# ai.net
KiCad netlist of a schematic drawn in Altium Designer
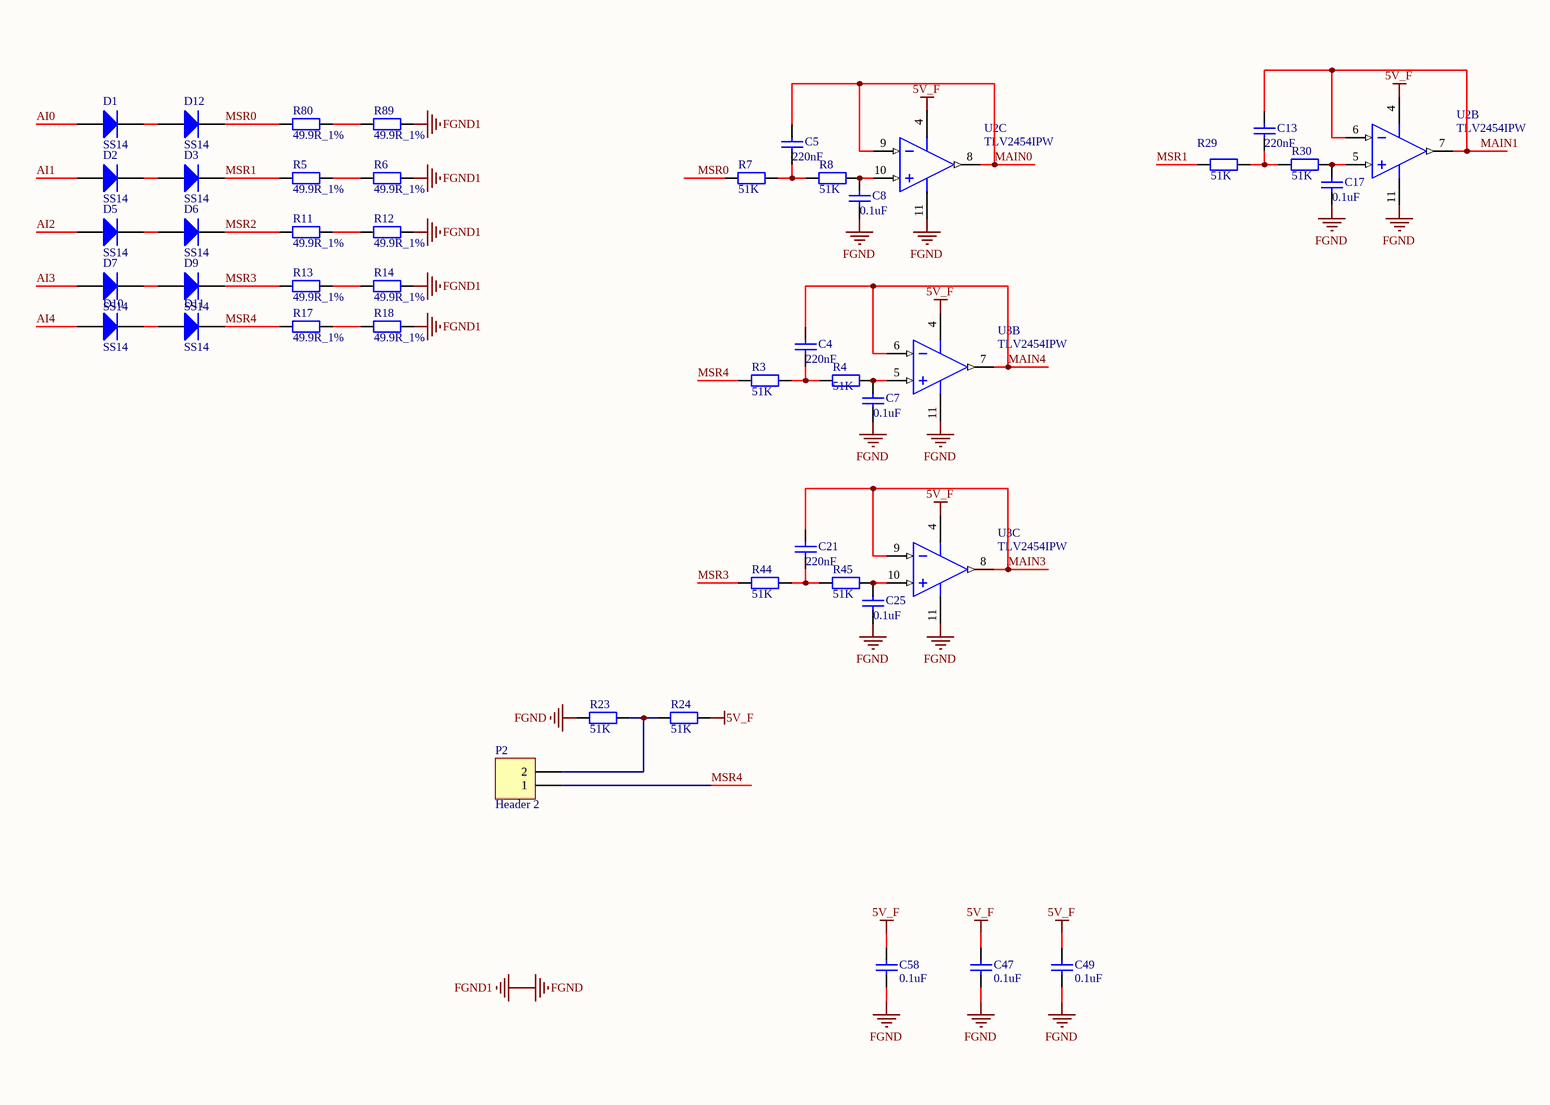
[diagram p0: ai.SchDoc, top left]
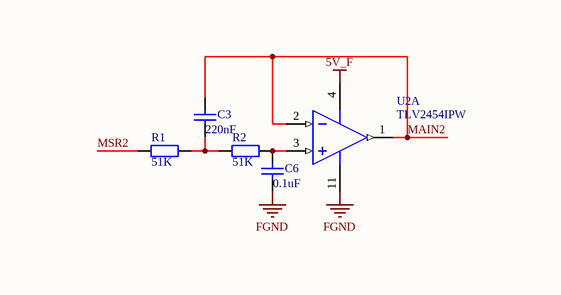
[diagram p1: ai.SchDoc, top right]
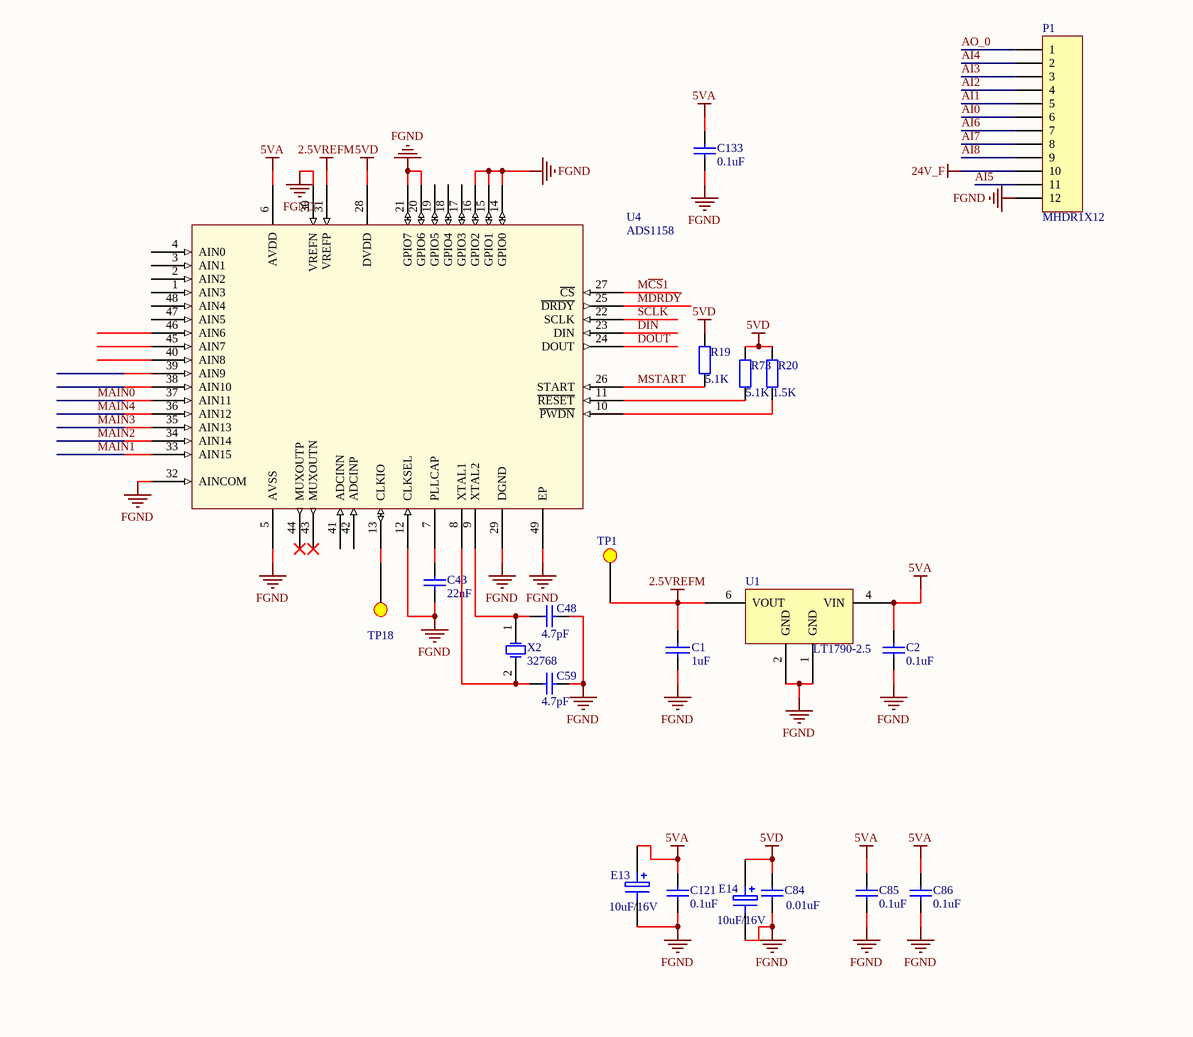
[diagram p2: ai.SchDoc, bottom left]
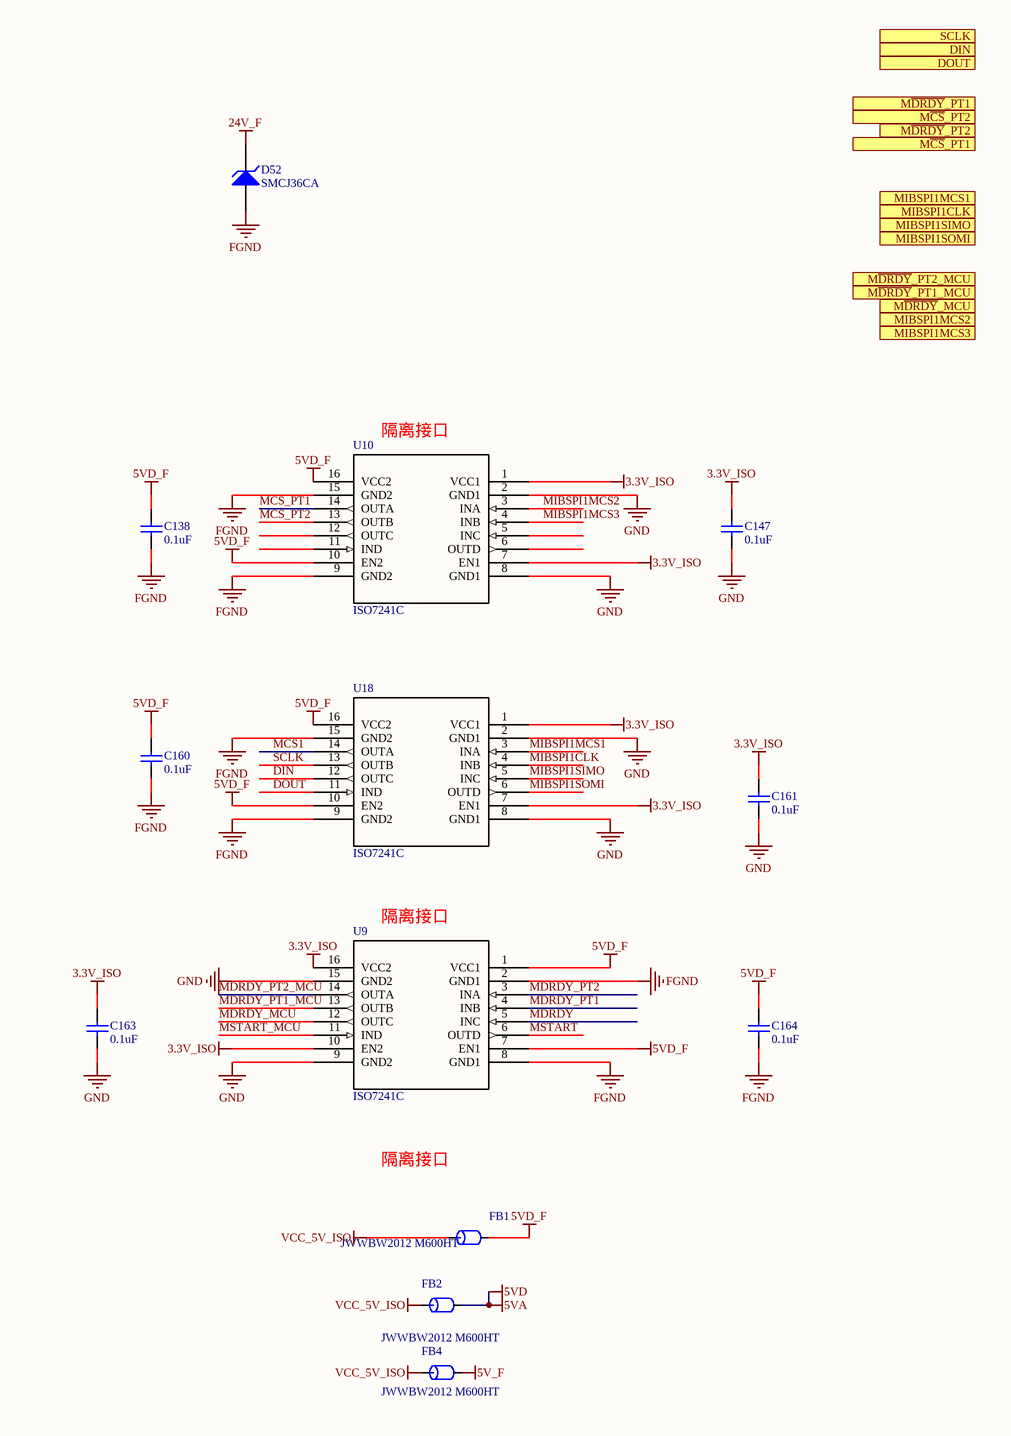
[diagram p3: ai.SchDoc, bottom right]

(export (version "E")
  (design (tool "Eeschema 10.0.6"))
  (components
    (comp (ref "C1")
      (value "1uF")
      (footprint "0603C")
      (description "Capacitor")
      (libsource (lib "*") (part "CAP"))
    )
    (comp (ref "C2")
      (value "0.1uF")
      (footprint "0603C")
      (description "Capacitor")
      (fields (field (name "PUBLISHER") "Altium Limited"))
      (libsource (lib "Miscellaneous Devices") (part "Cap"))
    )
    (comp (ref "C3")
      (value "220nF")
      (footprint "0805C")
      (description "Capacitor")
      (fields (field (name "PUBLISHER") "Altium Limited"))
      (libsource (lib "Miscellaneous Devices") (part "Cap"))
    )
    (comp (ref "C4")
      (value "220nF")
      (footprint "0805C")
      (description "Capacitor")
      (fields (field (name "PUBLISHER") "Altium Limited"))
      (libsource (lib "Miscellaneous Devices") (part "Cap"))
    )
    (comp (ref "C5")
      (value "220nF")
      (footprint "0805C")
      (description "Capacitor")
      (fields (field (name "PUBLISHER") "Altium Limited"))
      (libsource (lib "Miscellaneous Devices") (part "Cap"))
    )
    (comp (ref "C6")
      (value "0.1uF")
      (footprint "0603C")
      (description "Capacitor")
      (fields (field (name "PUBLISHER") "Altium Limited"))
      (libsource (lib "Miscellaneous Devices") (part "Cap"))
    )
    (comp (ref "C7")
      (value "0.1uF")
      (footprint "0603C")
      (description "Capacitor")
      (fields (field (name "PUBLISHER") "Altium Limited"))
      (libsource (lib "Miscellaneous Devices") (part "Cap"))
    )
    (comp (ref "C8")
      (value "0.1uF")
      (footprint "0603C")
      (description "Capacitor")
      (fields (field (name "PUBLISHER") "Altium Limited"))
      (libsource (lib "Miscellaneous Devices") (part "Cap"))
    )
    (comp (ref "C13")
      (value "220nF")
      (footprint "0805C")
      (description "Capacitor")
      (fields (field (name "PUBLISHER") "Altium Limited"))
      (libsource (lib "Miscellaneous Devices") (part "Cap"))
    )
    (comp (ref "C17")
      (value "0.1uF")
      (footprint "0603C")
      (description "Capacitor")
      (fields (field (name "PUBLISHER") "Altium Limited"))
      (libsource (lib "Miscellaneous Devices") (part "Cap"))
    )
    (comp (ref "C21")
      (value "220nF")
      (footprint "0805C")
      (description "Capacitor")
      (fields (field (name "PUBLISHER") "Altium Limited"))
      (libsource (lib "Miscellaneous Devices") (part "Cap"))
    )
    (comp (ref "C25")
      (value "0.1uF")
      (footprint "0603C")
      (description "Capacitor")
      (fields (field (name "PUBLISHER") "Altium Limited"))
      (libsource (lib "Miscellaneous Devices") (part "Cap"))
    )
    (comp (ref "C43")
      (value "22nF")
      (footprint "0805C")
      (description "Capacitor")
      (fields (field (name "PUBLISHER") "Altium Limited"))
      (libsource (lib "Miscellaneous Devices") (part "Cap"))
    )
    (comp (ref "C47")
      (value "0.1uF")
      (footprint "0603C")
      (description "Capacitor")
      (fields (field (name "PUBLISHER") "Altium Limited"))
      (libsource (lib "Miscellaneous Devices") (part "Cap"))
    )
    (comp (ref "C48")
      (value "4.7pF")
      (footprint "0603C")
      (description "Capacitor")
      (fields (field (name "PUBLISHER") "Altium Limited"))
      (libsource (lib "Miscellaneous Devices") (part "Cap"))
    )
    (comp (ref "C49")
      (value "0.1uF")
      (footprint "0603C")
      (description "Capacitor")
      (fields (field (name "PUBLISHER") "Altium Limited"))
      (libsource (lib "Miscellaneous Devices") (part "Cap"))
    )
    (comp (ref "C58")
      (value "0.1uF")
      (footprint "0603C")
      (description "Capacitor")
      (fields (field (name "PUBLISHER") "Altium Limited"))
      (libsource (lib "Miscellaneous Devices") (part "Cap"))
    )
    (comp (ref "C59")
      (value "4.7pF")
      (footprint "0603C")
      (description "Capacitor")
      (fields (field (name "PUBLISHER") "Altium Limited"))
      (libsource (lib "Miscellaneous Devices") (part "Cap"))
    )
    (comp (ref "C84")
      (value "0.01uF")
      (footprint "0603C")
      (description "Capacitor")
      (fields (field (name "PUBLISHER") "Altium Limited"))
      (libsource (lib "Miscellaneous Devices") (part "Cap"))
    )
    (comp (ref "C85")
      (value "0.1uF")
      (footprint "0603C")
      (description "Capacitor")
      (fields (field (name "PUBLISHER") "Altium Limited"))
      (libsource (lib "Miscellaneous Devices") (part "Cap"))
    )
    (comp (ref "C86")
      (value "0.1uF")
      (footprint "0603C")
      (description "Capacitor")
      (fields (field (name "PUBLISHER") "Altium Limited"))
      (libsource (lib "Miscellaneous Devices") (part "Cap"))
    )
    (comp (ref "C121")
      (value "0.1uF")
      (footprint "0603C")
      (description "Capacitor")
      (fields (field (name "PUBLISHER") "Altium Limited"))
      (libsource (lib "Miscellaneous Devices") (part "Cap"))
    )
    (comp (ref "C133")
      (value "0.1uF")
      (footprint "0603C")
      (description "Capacitor")
      (fields (field (name "PUBLISHER") "Altium Limited"))
      (libsource (lib "Miscellaneous Devices") (part "Cap"))
    )
    (comp (ref "C138")
      (value "0.1uF")
      (footprint "0603C")
      (description "Capacitor")
      (fields (field (name "PUBLISHER") "Altium Limited"))
      (libsource (lib "Miscellaneous Devices") (part "Cap"))
    )
    (comp (ref "C147")
      (value "0.1uF")
      (footprint "0603C")
      (description "Capacitor")
      (fields (field (name "PUBLISHER") "Altium Limited"))
      (libsource (lib "Miscellaneous Devices") (part "Cap"))
    )
    (comp (ref "C160")
      (value "0.1uF")
      (footprint "0603C")
      (description "Capacitor")
      (fields (field (name "PUBLISHER") "Altium Limited"))
      (libsource (lib "Miscellaneous Devices") (part "Cap"))
    )
    (comp (ref "C161")
      (value "0.1uF")
      (footprint "0603C")
      (description "Capacitor")
      (fields (field (name "PUBLISHER") "Altium Limited"))
      (libsource (lib "Miscellaneous Devices") (part "Cap"))
    )
    (comp (ref "C163")
      (value "0.1uF")
      (footprint "0603C")
      (description "Capacitor")
      (fields (field (name "PUBLISHER") "Altium Limited"))
      (libsource (lib "Miscellaneous Devices") (part "Cap"))
    )
    (comp (ref "C164")
      (value "0.1uF")
      (footprint "0603C")
      (description "Capacitor")
      (fields (field (name "PUBLISHER") "Altium Limited"))
      (libsource (lib "Miscellaneous Devices") (part "Cap"))
    )
    (comp (ref "D1")
      (value "SS14")
      (footprint "DO-214AC")
      (description "Default Diode")
      (fields (field (name "PUBLISHER") "Altium Limited"))
      (libsource (lib "Miscellaneous Devices") (part "Diode"))
    )
    (comp (ref "D2")
      (value "SS14")
      (footprint "DO-214AC")
      (description "Default Diode")
      (fields (field (name "PUBLISHER") "Altium Limited"))
      (libsource (lib "Miscellaneous Devices") (part "Diode"))
    )
    (comp (ref "D3")
      (value "SS14")
      (footprint "DO-214AC")
      (description "Default Diode")
      (fields (field (name "PUBLISHER") "Altium Limited"))
      (libsource (lib "Miscellaneous Devices") (part "Diode"))
    )
    (comp (ref "D5")
      (value "SS14")
      (footprint "DO-214AC")
      (description "Default Diode")
      (fields (field (name "PUBLISHER") "Altium Limited"))
      (libsource (lib "Miscellaneous Devices") (part "Diode"))
    )
    (comp (ref "D6")
      (value "SS14")
      (footprint "DO-214AC")
      (description "Default Diode")
      (fields (field (name "PUBLISHER") "Altium Limited"))
      (libsource (lib "Miscellaneous Devices") (part "Diode"))
    )
    (comp (ref "D7")
      (value "SS14")
      (footprint "DO-214AC")
      (description "Default Diode")
      (fields (field (name "PUBLISHER") "Altium Limited"))
      (libsource (lib "Miscellaneous Devices") (part "Diode"))
    )
    (comp (ref "D9")
      (value "SS14")
      (footprint "DO-214AC")
      (description "Default Diode")
      (fields (field (name "PUBLISHER") "Altium Limited"))
      (libsource (lib "Miscellaneous Devices") (part "Diode"))
    )
    (comp (ref "D10")
      (value "SS14")
      (footprint "DO-214AC")
      (description "Default Diode")
      (fields (field (name "PUBLISHER") "Altium Limited"))
      (libsource (lib "Miscellaneous Devices") (part "Diode"))
    )
    (comp (ref "D11")
      (value "SS14")
      (footprint "DO-214AC")
      (description "Default Diode")
      (fields (field (name "PUBLISHER") "Altium Limited"))
      (libsource (lib "Miscellaneous Devices") (part "Diode"))
    )
    (comp (ref "D12")
      (value "SS14")
      (footprint "DO-214AC")
      (description "Default Diode")
      (fields (field (name "PUBLISHER") "Altium Limited"))
      (libsource (lib "Miscellaneous Devices") (part "Diode"))
    )
    (comp (ref "D52")
      (value "SMCJ36CA")
      (footprint "SMC")
      (description "SMBJ36CA")
      (fields (field (name "PUBLISHER") "Altium Limited"))
      (libsource (lib "Miscellaneous Devices") (part "D Zener"))
    )
    (comp (ref "E13")
      (value "10uF/16V")
      (footprint "C3528")
      (description "Electrolytic Capacitor")
      (libsource (lib "*") (part "ELECTRO1"))
    )
    (comp (ref "E14")
      (value "10uF/16V")
      (footprint "C3528")
      (description "Electrolytic Capacitor")
      (libsource (lib "*") (part "ELECTRO1"))
    )
    (comp (ref "FB1")
      (value "JWWBW2012 M600HT")
      (footprint "0805R")
      (libsource (lib "Schlib_20110825") (part "FB"))
    )
    (comp (ref "FB2")
      (value "JWWBW2012 M600HT")
      (footprint "0805R")
      (libsource (lib "Schlib_20110825") (part "FB"))
    )
    (comp (ref "FB4")
      (value "JWWBW2012 M600HT")
      (footprint "0805R")
      (libsource (lib "Schlib_20110825") (part "FB"))
    )
    (comp (ref "P1")
      (value "MHDR1X12")
      (footprint "2ETYR-5.08-12P-14-100")
      (description "Header, 12-Pin")
      (fields (field (name "PUBLISHER") "Altium Limited"))
      (libsource (lib "Miscellaneous Connectors") (part "MHDR1X12"))
    )
    (comp (ref "P2")
      (value "Header 2")
      (footprint "HDR1X2")
      (description "Header, 2-Pin")
      (fields (field (name "PUBLISHER") "Altium Limited"))
      (libsource (lib "Miscellaneous Connectors") (part "Header 2"))
    )
    (comp (ref "R1") (value "51K") (footprint "0603R") (libsource (lib "MQlibrary") (part "Res0805M")))
    (comp (ref "R2") (value "51K") (footprint "0603R") (libsource (lib "MQlibrary") (part "Res0805M")))
    (comp (ref "R3") (value "51K") (footprint "0603R") (libsource (lib "MQlibrary") (part "Res0805M")))
    (comp (ref "R4") (value "51K") (footprint "0603R") (libsource (lib "MQlibrary") (part "Res0805M")))
    (comp (ref "R5") (value "49.9R_1%") (footprint "0805R") (libsource (lib "MQlibrary") (part "Res0805M")))
    (comp (ref "R6") (value "49.9R_1%") (footprint "0805R") (libsource (lib "MQlibrary") (part "Res0805M")))
    (comp (ref "R7") (value "51K") (footprint "0603R") (libsource (lib "MQlibrary") (part "Res0805M")))
    (comp (ref "R8") (value "51K") (footprint "0603R") (libsource (lib "MQlibrary") (part "Res0805M")))
    (comp (ref "R11") (value "49.9R_1%") (footprint "0805R") (libsource (lib "MQlibrary") (part "Res0805M")))
    (comp (ref "R12") (value "49.9R_1%") (footprint "0805R") (libsource (lib "MQlibrary") (part "Res0805M")))
    (comp (ref "R13") (value "49.9R_1%") (footprint "0805R") (libsource (lib "MQlibrary") (part "Res0805M")))
    (comp (ref "R14") (value "49.9R_1%") (footprint "0805R") (libsource (lib "MQlibrary") (part "Res0805M")))
    (comp (ref "R17") (value "49.9R_1%") (footprint "0805R") (libsource (lib "MQlibrary") (part "Res0805M")))
    (comp (ref "R18") (value "49.9R_1%") (footprint "0805R") (libsource (lib "MQlibrary") (part "Res0805M")))
    (comp (ref "R19") (value "5.1K") (footprint "0603R") (libsource (lib "") (part "Res0805M_2")))
    (comp (ref "R20") (value "1.5K") (footprint "0603R") (libsource (lib "") (part "Res0805M_2")))
    (comp (ref "R23") (value "51K") (footprint "0603R") (libsource (lib "") (part "Res0805M_1")))
    (comp (ref "R24") (value "51K") (footprint "0603R") (libsource (lib "") (part "Res0805M_1")))
    (comp (ref "R29") (value "51K") (footprint "0603R") (libsource (lib "MQlibrary") (part "Res0805M")))
    (comp (ref "R30") (value "51K") (footprint "0603R") (libsource (lib "MQlibrary") (part "Res0805M")))
    (comp (ref "R44") (value "51K") (footprint "0603R") (libsource (lib "MQlibrary") (part "Res0805M")))
    (comp (ref "R45") (value "51K") (footprint "0603R") (libsource (lib "MQlibrary") (part "Res0805M")))
    (comp (ref "R73") (value "5.1K") (footprint "0603R") (libsource (lib "") (part "Res0805M_2")))
    (comp (ref "R80") (value "49.9R_1%") (footprint "0805R") (libsource (lib "MQlibrary") (part "Res0805M")))
    (comp (ref "R89") (value "49.9R_1%") (footprint "0805R") (libsource (lib "MQlibrary") (part "Res0805M")))
    (comp (ref "TP1")
      (value "TEST_POINT")
      (footprint "TPD")
      (libsource (lib "基带芯片OEM板_V1P0_张猛_20120921") (part "TEST_POINT"))
    )
    (comp (ref "TP18")
      (value "TEST_POINT")
      (footprint "TPD")
      (libsource (lib "基带芯片OEM板_V1P0_张猛_20120921") (part "TEST_POINT"))
    )
    (comp (ref "U1")
      (value "LT1790-2.5")
      (footprint "SOT23-6")
      (description "2.5V Micropower SOT-23  Low Dropout Reference")
      (libsource (lib "Schlib") (part "LT1790-2.5"))
    )
    (comp (ref "U2")
      (value "TLV2454IPW")
      (footprint "TSSOP14")
      (description "Quad High-speed, Ultra Low-power, Single-Supply TTL comparator")
      (fields (field (name "PUBLISHER") "Altium Limited"))
      (libsource (lib "Maxim Analog Comparator") (part "MAX908EPD"))
    )
    (comp (ref "U3")
      (value "TLV2454IPW")
      (footprint "TSSOP14")
      (description "Quad High-speed, Ultra Low-power, Single-Supply TTL comparator")
      (fields (field (name "PUBLISHER") "Altium Limited"))
      (libsource (lib "Maxim Analog Comparator") (part "MAX908EPD"))
    )
    (comp (ref "U4")
      (value "ADS1158")
      (footprint "S-PVFQN-N48")
      (description "16-Channel, 16-Bit Analog-to-Digital Converter")
      (libsource (lib "Schlib") (part "ADS1158"))
    )
    (comp (ref "U9") (value "ISO7241C") (footprint "SOIC16") (libsource (lib "DI16") (part "ISO7241C")))
    (comp (ref "U10") (value "ISO7241C") (footprint "SOIC16") (libsource (lib "DI16") (part "ISO7241C")))
    (comp (ref "U18") (value "ISO7241C") (footprint "SOIC16") (libsource (lib "DI16") (part "ISO7241C")))
    (comp (ref "X2")
      (value "32768")
      (footprint "A")
      (description "Crystal Oscillator")
      (fields (field (name "PUBLISHER") "Altium Limited"))
      (libsource (lib "Miscellaneous Devices") (part "XTAL"))
    )
  )
  (nets
    (net (code "1") (name "/AI0") (class "Default")
      (node (ref "D1") (pin "1") (pinfunction "A_1") (pintype "passive"))
      (node (ref "P1") (pin "6") (pinfunction "6_6") (pintype "passive"))
    )
    (net (code "2") (name "/AI1") (class "Default")
      (node (ref "D2") (pin "1") (pinfunction "A_1") (pintype "passive"))
      (node (ref "P1") (pin "5") (pinfunction "5_5") (pintype "passive"))
    )
    (net (code "3") (name "/AI2") (class "Default")
      (node (ref "D5") (pin "1") (pinfunction "A_1") (pintype "passive"))
      (node (ref "P1") (pin "4") (pinfunction "4_4") (pintype "passive"))
    )
    (net (code "4") (name "/AI3") (class "Default")
      (node (ref "D7") (pin "1") (pinfunction "A_1") (pintype "passive"))
      (node (ref "P1") (pin "3") (pinfunction "3_3") (pintype "passive"))
    )
    (net (code "5") (name "/AI4") (class "Default")
      (node (ref "D10") (pin "1") (pinfunction "A_1") (pintype "passive"))
      (node (ref "P1") (pin "2") (pinfunction "2_2") (pintype "passive"))
    )
    (net (code "6") (name "/AI5") (class "Default")
      (node (ref "P1") (pin "11") (pinfunction "11_11") (pintype "passive"))
    )
    (net (code "7") (name "/AI6") (class "Default")
      (node (ref "P1") (pin "7") (pinfunction "7_7") (pintype "passive"))
    )
    (net (code "8") (name "/AI7") (class "Default")
      (node (ref "P1") (pin "8") (pinfunction "8_8") (pintype "passive"))
    )
    (net (code "9") (name "/AI8") (class "Default")
      (node (ref "P1") (pin "9") (pinfunction "9_9") (pintype "passive"))
    )
    (net (code "10") (name "/AO_0") (class "Default")
      (node (ref "P1") (pin "1") (pinfunction "1_1") (pintype "passive"))
    )
    (net (code "11") (name "/DIN") (class "Default")
      (node (ref "U18") (pin "12") (pinfunction "OUTC_12") (pintype "output"))
      (node (ref "U4") (pin "23") (pinfunction "DIN_23") (pintype "input"))
    )
    (net (code "12") (name "/DOUT") (class "Default")
      (node (ref "U18") (pin "11") (pinfunction "IND_11") (pintype "input"))
      (node (ref "U4") (pin "24") (pinfunction "DOUT_24") (pintype "output"))
    )
    (net (code "13") (name "/MAIN0") (class "Default")
      (node (ref "C5") (pin "2") (pinfunction "2_2") (pintype "passive"))
      (node (ref "U2") (pin "8") (pinfunction "OUT_8") (pintype "output"))
      (node (ref "U2") (pin "9") (pinfunction "IN-_9") (pintype "input"))
      (node (ref "U4") (pin "37") (pinfunction "AIN11_37") (pintype "input"))
    )
    (net (code "14") (name "/MAIN1") (class "Default")
      (node (ref "C13") (pin "2") (pinfunction "2_2") (pintype "passive"))
      (node (ref "U2") (pin "6") (pinfunction "IN-_6") (pintype "input"))
      (node (ref "U2") (pin "7") (pinfunction "OUT_7") (pintype "output"))
      (node (ref "U4") (pin "33") (pinfunction "AIN15_33") (pintype "input"))
    )
    (net (code "15") (name "/MAIN2") (class "Default")
      (node (ref "C3") (pin "2") (pinfunction "2_2") (pintype "passive"))
      (node (ref "U2") (pin "1") (pinfunction "OUT_1") (pintype "output"))
      (node (ref "U2") (pin "2") (pinfunction "IN-_2") (pintype "input"))
      (node (ref "U4") (pin "34") (pinfunction "AIN14_34") (pintype "input"))
    )
    (net (code "16") (name "/MAIN3") (class "Default")
      (node (ref "C21") (pin "2") (pinfunction "2_2") (pintype "passive"))
      (node (ref "U3") (pin "8") (pinfunction "OUT_8") (pintype "output"))
      (node (ref "U3") (pin "9") (pinfunction "IN-_9") (pintype "input"))
      (node (ref "U4") (pin "35") (pinfunction "AIN13_35") (pintype "input"))
    )
    (net (code "17") (name "/MAIN4") (class "Default")
      (node (ref "C4") (pin "2") (pinfunction "2_2") (pintype "passive"))
      (node (ref "U3") (pin "6") (pinfunction "IN-_6") (pintype "input"))
      (node (ref "U3") (pin "7") (pinfunction "OUT_7") (pintype "output"))
      (node (ref "U4") (pin "36") (pinfunction "AIN12_36") (pintype "input"))
    )
    (net (code "18") (name "/MIBSPI1CLK") (class "Default")
      (node (ref "U18") (pin "4") (pinfunction "INB_4") (pintype "input"))
    )
    (net (code "19") (name "/MIBSPI1MCS1") (class "Default")
      (node (ref "U18") (pin "3") (pinfunction "INA_3") (pintype "input"))
    )
    (net (code "20") (name "/MIBSPI1MCS2") (class "Default")
      (node (ref "U10") (pin "3") (pinfunction "INA_3") (pintype "input"))
    )
    (net (code "21") (name "/MIBSPI1MCS3") (class "Default")
      (node (ref "U10") (pin "4") (pinfunction "INB_4") (pintype "input"))
    )
    (net (code "22") (name "/MIBSPI1SIMO") (class "Default")
      (node (ref "U18") (pin "5") (pinfunction "INC_5") (pintype "input"))
    )
    (net (code "23") (name "/MIBSPI1SOMI") (class "Default")
      (node (ref "U18") (pin "6") (pinfunction "OUTD_6") (pintype "output"))
    )
    (net (code "24") (name "/MSR0") (class "Default")
      (node (ref "D12") (pin "2") (pinfunction "K_2") (pintype "passive"))
      (node (ref "R7") (pin "2") (pinfunction "2_2") (pintype "passive"))
      (node (ref "R80") (pin "2") (pinfunction "2_2") (pintype "passive"))
    )
    (net (code "25") (name "/MSR1") (class "Default")
      (node (ref "D3") (pin "2") (pinfunction "K_2") (pintype "passive"))
      (node (ref "R29") (pin "2") (pinfunction "2_2") (pintype "passive"))
      (node (ref "R5") (pin "2") (pinfunction "2_2") (pintype "passive"))
    )
    (net (code "26") (name "/MSR2") (class "Default")
      (node (ref "D6") (pin "2") (pinfunction "K_2") (pintype "passive"))
      (node (ref "R1") (pin "2") (pinfunction "2_2") (pintype "passive"))
      (node (ref "R11") (pin "2") (pinfunction "2_2") (pintype "passive"))
    )
    (net (code "27") (name "/MSR3") (class "Default")
      (node (ref "D9") (pin "2") (pinfunction "K_2") (pintype "passive"))
      (node (ref "R13") (pin "2") (pinfunction "2_2") (pintype "passive"))
      (node (ref "R44") (pin "2") (pinfunction "2_2") (pintype "passive"))
    )
    (net (code "28") (name "/MSR4") (class "Default")
      (node (ref "D11") (pin "2") (pinfunction "K_2") (pintype "passive"))
      (node (ref "P2") (pin "1") (pinfunction "1_1") (pintype "passive"))
      (node (ref "R17") (pin "2") (pinfunction "2_2") (pintype "passive"))
      (node (ref "R3") (pin "2") (pinfunction "2_2") (pintype "passive"))
    )
    (net (code "29") (name "/MSTART") (class "Default")
      (node (ref "R19") (pin "2") (pinfunction "2_2") (pintype "passive"))
      (node (ref "U4") (pin "26") (pinfunction "START_26") (pintype "input"))
      (node (ref "U9") (pin "6") (pinfunction "OUTD_6") (pintype "output"))
    )
    (net (code "30") (name "/MSTART_MCU") (class "Default")
      (node (ref "U9") (pin "11") (pinfunction "IND_11") (pintype "input"))
    )
    (net (code "31") (name "/M~{CS}1") (class "Default")
      (node (ref "U18") (pin "14") (pinfunction "OUTA_14") (pintype "output"))
      (node (ref "U4") (pin "27") (pinfunction "~{CS}_27") (pintype "input"))
    )
    (net (code "32") (name "/M~{CS}_PT1") (class "Default")
      (node (ref "U10") (pin "14") (pinfunction "OUTA_14") (pintype "output"))
    )
    (net (code "33") (name "/M~{CS}_PT2") (class "Default")
      (node (ref "U10") (pin "13") (pinfunction "OUTB_13") (pintype "output"))
    )
    (net (code "34") (name "/M~{DRDY}") (class "Default")
      (node (ref "U4") (pin "25") (pinfunction "~{DRDY}_25") (pintype "output"))
      (node (ref "U9") (pin "5") (pinfunction "INC_5") (pintype "input"))
    )
    (net (code "35") (name "/M~{DRDY}_MCU") (class "Default")
      (node (ref "U9") (pin "12") (pinfunction "OUTC_12") (pintype "output"))
    )
    (net (code "36") (name "/M~{DRDY}_PT1") (class "Default")
      (node (ref "U9") (pin "4") (pinfunction "INB_4") (pintype "input"))
    )
    (net (code "37") (name "/M~{DRDY}_PT1_MCU") (class "Default")
      (node (ref "U9") (pin "13") (pinfunction "OUTB_13") (pintype "output"))
    )
    (net (code "38") (name "/M~{DRDY}_PT2") (class "Default")
      (node (ref "U9") (pin "3") (pinfunction "INA_3") (pintype "input"))
    )
    (net (code "39") (name "/M~{DRDY}_PT2_MCU") (class "Default")
      (node (ref "U9") (pin "14") (pinfunction "OUTA_14") (pintype "output"))
    )
    (net (code "40") (name "/SCLK") (class "Default")
      (node (ref "U18") (pin "13") (pinfunction "OUTB_13") (pintype "output"))
      (node (ref "U4") (pin "22") (pinfunction "SCLK_22") (pintype "input"))
    )
    (net (code "41") (name "2.5VREFM") (class "Default")
      (node (ref "C1") (pin "1") (pinfunction "1_1") (pintype "passive"))
      (node (ref "TP1") (pin "1") (pinfunction "1_1") (pintype "passive"))
      (node (ref "U1") (pin "6") (pinfunction "VOUT_6") (pintype "power_in"))
      (node (ref "U4") (pin "31") (pinfunction "VREFP_31") (pintype "input"))
    )
    (net (code "42") (name "3.3V_ISO") (class "Default")
      (node (ref "C147") (pin "2") (pinfunction "2_2") (pintype "passive"))
      (node (ref "C161") (pin "2") (pinfunction "2_2") (pintype "passive"))
      (node (ref "C163") (pin "2") (pinfunction "2_2") (pintype "passive"))
      (node (ref "U10") (pin "1") (pinfunction "VCC1_1") (pintype "power_in"))
      (node (ref "U10") (pin "7") (pinfunction "EN1_7") (pintype "passive"))
      (node (ref "U18") (pin "1") (pinfunction "VCC1_1") (pintype "power_in"))
      (node (ref "U18") (pin "7") (pinfunction "EN1_7") (pintype "passive"))
      (node (ref "U9") (pin "10") (pinfunction "EN2_10") (pintype "passive"))
      (node (ref "U9") (pin "16") (pinfunction "VCC2_16") (pintype "power_in"))
    )
    (net (code "43") (name "5VA") (class "Default")
      (node (ref "C121") (pin "2") (pinfunction "2_2") (pintype "passive"))
      (node (ref "C133") (pin "2") (pinfunction "2_2") (pintype "passive"))
      (node (ref "C2") (pin "2") (pinfunction "2_2") (pintype "passive"))
      (node (ref "C84") (pin "2") (pinfunction "2_2") (pintype "passive"))
      (node (ref "C85") (pin "2") (pinfunction "2_2") (pintype "passive"))
      (node (ref "C86") (pin "2") (pinfunction "2_2") (pintype "passive"))
      (node (ref "E13") (pin "1") (pinfunction "1_1") (pintype "passive"))
      (node (ref "E14") (pin "1") (pinfunction "1_1") (pintype "passive"))
      (node (ref "FB2") (pin "2") (pintype "passive"))
      (node (ref "R19") (pin "1") (pinfunction "1_1") (pintype "passive"))
      (node (ref "R20") (pin "1") (pinfunction "1_1") (pintype "passive"))
      (node (ref "R73") (pin "1") (pinfunction "1_1") (pintype "passive"))
      (node (ref "U1") (pin "4") (pinfunction "VIN_4") (pintype "power_in"))
      (node (ref "U4") (pin "28") (pinfunction "DVDD_28") (pintype "power_in"))
      (node (ref "U4") (pin "6") (pinfunction "AVDD_6") (pintype "passive"))
    )
    (net (code "44") (name "5VD_F") (class "Default")
      (node (ref "C138") (pin "2") (pinfunction "2_2") (pintype "passive"))
      (node (ref "C160") (pin "2") (pinfunction "2_2") (pintype "passive"))
      (node (ref "C164") (pin "2") (pinfunction "2_2") (pintype "passive"))
      (node (ref "FB1") (pin "2") (pintype "passive"))
      (node (ref "U10") (pin "10") (pinfunction "EN2_10") (pintype "passive"))
      (node (ref "U10") (pin "16") (pinfunction "VCC2_16") (pintype "power_in"))
      (node (ref "U18") (pin "10") (pinfunction "EN2_10") (pintype "passive"))
      (node (ref "U18") (pin "16") (pinfunction "VCC2_16") (pintype "power_in"))
      (node (ref "U9") (pin "1") (pinfunction "VCC1_1") (pintype "power_in"))
      (node (ref "U9") (pin "7") (pinfunction "EN1_7") (pintype "passive"))
    )
    (net (code "45") (name "5V_F") (class "Default")
      (node (ref "C47") (pin "2") (pinfunction "2_2") (pintype "passive"))
      (node (ref "C49") (pin "2") (pinfunction "2_2") (pintype "passive"))
      (node (ref "C58") (pin "2") (pinfunction "2_2") (pintype "passive"))
      (node (ref "FB4") (pin "2") (pintype "passive"))
      (node (ref "R24") (pin "2") (pinfunction "2_2") (pintype "passive"))
      (node (ref "U2") (pin "4") (pinfunction "V+_4") (pintype "power_in"))
      (node (ref "U3") (pin "4") (pinfunction "V+_4") (pintype "power_in"))
    )
    (net (code "46") (name "24V_F") (class "Default")
      (node (ref "D52") (pin "2") (pinfunction "K_2") (pintype "passive"))
      (node (ref "P1") (pin "10") (pinfunction "10_10") (pintype "passive"))
    )
    (net (code "47") (name "FGND") (class "Default")
      (node (ref "C1") (pin "2") (pinfunction "2_2") (pintype "passive"))
      (node (ref "C121") (pin "1") (pinfunction "1_1") (pintype "passive"))
      (node (ref "C133") (pin "1") (pinfunction "1_1") (pintype "passive"))
      (node (ref "C138") (pin "1") (pinfunction "1_1") (pintype "passive"))
      (node (ref "C160") (pin "1") (pinfunction "1_1") (pintype "passive"))
      (node (ref "C164") (pin "1") (pinfunction "1_1") (pintype "passive"))
      (node (ref "C17") (pin "1") (pinfunction "1_1") (pintype "passive"))
      (node (ref "C2") (pin "1") (pinfunction "1_1") (pintype "passive"))
      (node (ref "C25") (pin "1") (pinfunction "1_1") (pintype "passive"))
      (node (ref "C43") (pin "2") (pinfunction "2_2") (pintype "passive"))
      (node (ref "C47") (pin "1") (pinfunction "1_1") (pintype "passive"))
      (node (ref "C48") (pin "2") (pinfunction "2_2") (pintype "passive"))
      (node (ref "C49") (pin "1") (pinfunction "1_1") (pintype "passive"))
      (node (ref "C58") (pin "1") (pinfunction "1_1") (pintype "passive"))
      (node (ref "C59") (pin "2") (pinfunction "2_2") (pintype "passive"))
      (node (ref "C6") (pin "1") (pinfunction "1_1") (pintype "passive"))
      (node (ref "C7") (pin "1") (pinfunction "1_1") (pintype "passive"))
      (node (ref "C8") (pin "1") (pinfunction "1_1") (pintype "passive"))
      (node (ref "C84") (pin "1") (pinfunction "1_1") (pintype "passive"))
      (node (ref "C85") (pin "1") (pinfunction "1_1") (pintype "passive"))
      (node (ref "C86") (pin "1") (pinfunction "1_1") (pintype "passive"))
      (node (ref "D52") (pin "1") (pinfunction "A_1") (pintype "passive"))
      (node (ref "E13") (pin "2") (pinfunction "2_2") (pintype "passive"))
      (node (ref "E14") (pin "2") (pinfunction "2_2") (pintype "passive"))
      (node (ref "P1") (pin "12") (pinfunction "12_12") (pintype "passive"))
      (node (ref "R12") (pin "1") (pinfunction "1_1") (pintype "passive"))
      (node (ref "R14") (pin "1") (pinfunction "1_1") (pintype "passive"))
      (node (ref "R18") (pin "1") (pinfunction "1_1") (pintype "passive"))
      (node (ref "R23") (pin "1") (pinfunction "1_1") (pintype "passive"))
      (node (ref "R6") (pin "1") (pinfunction "1_1") (pintype "passive"))
      (node (ref "R89") (pin "1") (pinfunction "1_1") (pintype "passive"))
      (node (ref "U1") (pin "1") (pinfunction "GND_1") (pintype "power_in"))
      (node (ref "U1") (pin "2") (pinfunction "GND_2") (pintype "power_in"))
      (node (ref "U10") (pin "15") (pinfunction "GND2_15") (pintype "power_in"))
      (node (ref "U10") (pin "9") (pinfunction "GND2_9") (pintype "power_in"))
      (node (ref "U18") (pin "15") (pinfunction "GND2_15") (pintype "power_in"))
      (node (ref "U18") (pin "9") (pinfunction "GND2_9") (pintype "power_in"))
      (node (ref "U2") (pin "11") (pinfunction "GND_11") (pintype "power_in"))
      (node (ref "U3") (pin "11") (pinfunction "GND_11") (pintype "power_in"))
      (node (ref "U4") (pin "12") (pinfunction "CLKSEL_12") (pintype "input"))
      (node (ref "U4") (pin "14") (pinfunction "GPIO0_14") (pintype "bidirectional"))
      (node (ref "U4") (pin "15") (pinfunction "GPIO1_15") (pintype "bidirectional"))
      (node (ref "U4") (pin "16") (pinfunction "GPIO2_16") (pintype "bidirectional"))
      (node (ref "U4") (pin "20") (pinfunction "GPIO6_20") (pintype "bidirectional"))
      (node (ref "U4") (pin "21") (pinfunction "GPIO7_21") (pintype "bidirectional"))
      (node (ref "U4") (pin "29") (pinfunction "DGND_29") (pintype "power_in"))
      (node (ref "U4") (pin "30") (pinfunction "VREFN_30") (pintype "input"))
      (node (ref "U4") (pin "32") (pinfunction "AINCOM_32") (pintype "input"))
      (node (ref "U4") (pin "49") (pinfunction "EP_49") (pintype "passive"))
      (node (ref "U4") (pin "5") (pinfunction "AVSS_5") (pintype "power_in"))
      (node (ref "U9") (pin "2") (pinfunction "GND1_2") (pintype "power_in"))
      (node (ref "U9") (pin "8") (pinfunction "GND1_8") (pintype "power_in"))
    )
    (net (code "48") (name "GND") (class "Default")
      (node (ref "C147") (pin "1") (pinfunction "1_1") (pintype "passive"))
      (node (ref "C161") (pin "1") (pinfunction "1_1") (pintype "passive"))
      (node (ref "C163") (pin "1") (pinfunction "1_1") (pintype "passive"))
      (node (ref "U10") (pin "2") (pinfunction "GND1_2") (pintype "power_in"))
      (node (ref "U10") (pin "8") (pinfunction "GND1_8") (pintype "power_in"))
      (node (ref "U18") (pin "2") (pinfunction "GND1_2") (pintype "power_in"))
      (node (ref "U18") (pin "8") (pinfunction "GND1_8") (pintype "power_in"))
      (node (ref "U9") (pin "15") (pinfunction "GND2_15") (pintype "power_in"))
      (node (ref "U9") (pin "9") (pinfunction "GND2_9") (pintype "power_in"))
    )
    (net (code "49") (name "Net-(C3-Pad1)") (class "Default")
      (node (ref "C3") (pin "1") (pinfunction "1_1") (pintype "passive"))
      (node (ref "R1") (pin "1") (pinfunction "1_1") (pintype "passive"))
      (node (ref "R2") (pin "2") (pinfunction "2_2") (pintype "passive"))
    )
    (net (code "50") (name "Net-(C4-Pad1)") (class "Default")
      (node (ref "C4") (pin "1") (pinfunction "1_1") (pintype "passive"))
      (node (ref "R3") (pin "1") (pinfunction "1_1") (pintype "passive"))
      (node (ref "R4") (pin "2") (pinfunction "2_2") (pintype "passive"))
    )
    (net (code "51") (name "Net-(C5-Pad1)") (class "Default")
      (node (ref "C5") (pin "1") (pinfunction "1_1") (pintype "passive"))
      (node (ref "R7") (pin "1") (pinfunction "1_1") (pintype "passive"))
      (node (ref "R8") (pin "2") (pinfunction "2_2") (pintype "passive"))
    )
    (net (code "52") (name "Net-(C13-Pad1)") (class "Default")
      (node (ref "C13") (pin "1") (pinfunction "1_1") (pintype "passive"))
      (node (ref "R29") (pin "1") (pinfunction "1_1") (pintype "passive"))
      (node (ref "R30") (pin "2") (pinfunction "2_2") (pintype "passive"))
    )
    (net (code "53") (name "Net-(C21-Pad1)") (class "Default")
      (node (ref "C21") (pin "1") (pinfunction "1_1") (pintype "passive"))
      (node (ref "R44") (pin "1") (pinfunction "1_1") (pintype "passive"))
      (node (ref "R45") (pin "2") (pinfunction "2_2") (pintype "passive"))
    )
    (net (code "54") (name "Net-(D1-K)") (class "Default")
      (node (ref "D1") (pin "2") (pinfunction "K_2") (pintype "passive"))
      (node (ref "D12") (pin "1") (pinfunction "A_1") (pintype "passive"))
    )
    (net (code "55") (name "Net-(D2-K)") (class "Default")
      (node (ref "D2") (pin "2") (pinfunction "K_2") (pintype "passive"))
      (node (ref "D3") (pin "1") (pinfunction "A_1") (pintype "passive"))
    )
    (net (code "56") (name "Net-(D5-K)") (class "Default")
      (node (ref "D5") (pin "2") (pinfunction "K_2") (pintype "passive"))
      (node (ref "D6") (pin "1") (pinfunction "A_1") (pintype "passive"))
    )
    (net (code "57") (name "Net-(D7-K)") (class "Default")
      (node (ref "D7") (pin "2") (pinfunction "K_2") (pintype "passive"))
      (node (ref "D9") (pin "1") (pinfunction "A_1") (pintype "passive"))
    )
    (net (code "58") (name "Net-(D10-K)") (class "Default")
      (node (ref "D10") (pin "2") (pinfunction "K_2") (pintype "passive"))
      (node (ref "D11") (pin "1") (pinfunction "A_1") (pintype "passive"))
    )
    (net (code "59") (name "Net-(P2-Pad2)") (class "Default")
      (node (ref "P2") (pin "2") (pinfunction "2_2") (pintype "passive"))
      (node (ref "R23") (pin "2") (pinfunction "2_2") (pintype "passive"))
      (node (ref "R24") (pin "1") (pinfunction "1_1") (pintype "passive"))
    )
    (net (code "60") (name "Net-(R5-Pad1)") (class "Default")
      (node (ref "R5") (pin "1") (pinfunction "1_1") (pintype "passive"))
      (node (ref "R6") (pin "2") (pinfunction "2_2") (pintype "passive"))
    )
    (net (code "61") (name "Net-(R11-Pad1)") (class "Default")
      (node (ref "R11") (pin "1") (pinfunction "1_1") (pintype "passive"))
      (node (ref "R12") (pin "2") (pinfunction "2_2") (pintype "passive"))
    )
    (net (code "62") (name "Net-(R13-Pad1)") (class "Default")
      (node (ref "R13") (pin "1") (pinfunction "1_1") (pintype "passive"))
      (node (ref "R14") (pin "2") (pinfunction "2_2") (pintype "passive"))
    )
    (net (code "63") (name "Net-(R17-Pad1)") (class "Default")
      (node (ref "R17") (pin "1") (pinfunction "1_1") (pintype "passive"))
      (node (ref "R18") (pin "2") (pinfunction "2_2") (pintype "passive"))
    )
    (net (code "64") (name "Net-(R80-Pad1)") (class "Default")
      (node (ref "R80") (pin "1") (pinfunction "1_1") (pintype "passive"))
      (node (ref "R89") (pin "2") (pinfunction "2_2") (pintype "passive"))
    )
    (net (code "65") (name "Net-(U2A-IN+)") (class "Default")
      (node (ref "C6") (pin "2") (pinfunction "2_2") (pintype "passive"))
      (node (ref "R2") (pin "1") (pinfunction "1_1") (pintype "passive"))
      (node (ref "U2") (pin "3") (pinfunction "IN+_3") (pintype "input"))
    )
    (net (code "66") (name "Net-(U2B-IN+)") (class "Default")
      (node (ref "C17") (pin "2") (pinfunction "2_2") (pintype "passive"))
      (node (ref "R30") (pin "1") (pinfunction "1_1") (pintype "passive"))
      (node (ref "U2") (pin "5") (pinfunction "IN+_5") (pintype "input"))
    )
    (net (code "67") (name "Net-(U2C-IN+)") (class "Default")
      (node (ref "C8") (pin "2") (pinfunction "2_2") (pintype "passive"))
      (node (ref "R8") (pin "1") (pinfunction "1_1") (pintype "passive"))
      (node (ref "U2") (pin "10") (pinfunction "IN+_10") (pintype "input"))
    )
    (net (code "68") (name "Net-(U3B-IN+)") (class "Default")
      (node (ref "C7") (pin "2") (pinfunction "2_2") (pintype "passive"))
      (node (ref "R4") (pin "1") (pinfunction "1_1") (pintype "passive"))
      (node (ref "U3") (pin "5") (pinfunction "IN+_5") (pintype "input"))
    )
    (net (code "69") (name "Net-(U3C-IN+)") (class "Default")
      (node (ref "C25") (pin "2") (pinfunction "2_2") (pintype "passive"))
      (node (ref "R45") (pin "1") (pinfunction "1_1") (pintype "passive"))
      (node (ref "U3") (pin "10") (pinfunction "IN+_10") (pintype "input"))
    )
    (net (code "70") (name "Net-(U4-CLKIO)") (class "Default")
      (node (ref "TP18") (pin "1") (pinfunction "1_1") (pintype "passive"))
      (node (ref "U4") (pin "13") (pinfunction "CLKIO_13") (pintype "bidirectional"))
    )
    (net (code "71") (name "Net-(U4-PLLCAP)") (class "Default")
      (node (ref "C43") (pin "1") (pinfunction "1_1") (pintype "passive"))
      (node (ref "U4") (pin "7") (pinfunction "PLLCAP_7") (pintype "power_in"))
    )
    (net (code "72") (name "Net-(U4-XTAL1)") (class "Default")
      (node (ref "C59") (pin "1") (pinfunction "1_1") (pintype "passive"))
      (node (ref "U4") (pin "8") (pinfunction "XTAL1_8") (pintype "passive"))
      (node (ref "X2") (pin "2") (pinfunction "OSC2_2") (pintype "passive"))
    )
    (net (code "73") (name "Net-(U4-XTAL2)") (class "Default")
      (node (ref "C48") (pin "1") (pinfunction "1_1") (pintype "passive"))
      (node (ref "U4") (pin "9") (pinfunction "XTAL2_9") (pintype "passive"))
      (node (ref "X2") (pin "1") (pinfunction "OSC1_1") (pintype "passive"))
    )
    (net (code "74") (name "Net-(U4-~{PWDN})") (class "Default")
      (node (ref "R20") (pin "2") (pinfunction "2_2") (pintype "passive"))
      (node (ref "U4") (pin "10") (pinfunction "~{PWDN}_10") (pintype "input"))
    )
    (net (code "75") (name "Net-(U4-~{RESET})") (class "Default")
      (node (ref "R73") (pin "2") (pinfunction "2_2") (pintype "passive"))
      (node (ref "U4") (pin "11") (pinfunction "~{RESET}_11") (pintype "input"))
    )
    (net (code "76") (name "VCC_5V_ISO") (class "Default")
      (node (ref "FB1") (pin "1") (pintype "passive"))
      (node (ref "FB2") (pin "1") (pintype "passive"))
      (node (ref "FB4") (pin "1") (pintype "passive"))
    )
    (net (code "77") (name "unconnected-(U1-DNC-Pad3)") (class "Default")
      (node (ref "U1") (pin "3") (pinfunction "DNC_3") (pintype "passive"))
    )
    (net (code "78") (name "unconnected-(U1-DNC-Pad5)") (class "Default")
      (node (ref "U1") (pin "5") (pinfunction "DNC_5") (pintype "passive"))
    )
    (net (code "79") (name "unconnected-(U4-ADCINN-Pad41)") (class "Default")
      (node (ref "U4") (pin "41") (pinfunction "ADCINN_41") (pintype "input"))
    )
    (net (code "80") (name "unconnected-(U4-ADCINP-Pad42)") (class "Default")
      (node (ref "U4") (pin "42") (pinfunction "ADCINP_42") (pintype "input"))
    )
    (net (code "81") (name "unconnected-(U4-AIN0-Pad4)") (class "Default")
      (node (ref "U4") (pin "4") (pinfunction "AIN0_4") (pintype "input"))
    )
    (net (code "82") (name "unconnected-(U4-AIN1-Pad3)") (class "Default")
      (node (ref "U4") (pin "3") (pinfunction "AIN1_3") (pintype "input"))
    )
    (net (code "83") (name "unconnected-(U4-AIN2-Pad2)") (class "Default")
      (node (ref "U4") (pin "2") (pinfunction "AIN2_2") (pintype "input"))
    )
    (net (code "84") (name "unconnected-(U4-AIN3-Pad1)") (class "Default")
      (node (ref "U4") (pin "1") (pinfunction "AIN3_1") (pintype "input"))
    )
    (net (code "85") (name "unconnected-(U4-AIN4-Pad48)") (class "Default")
      (node (ref "U4") (pin "48") (pinfunction "AIN4_48") (pintype "input"))
    )
    (net (code "86") (name "unconnected-(U4-AIN5-Pad47)") (class "Default")
      (node (ref "U4") (pin "47") (pinfunction "AIN5_47") (pintype "input"))
    )
    (net (code "87") (name "unconnected-(U4-AIN6-Pad46)") (class "Default")
      (node (ref "U4") (pin "46") (pinfunction "AIN6_46") (pintype "input"))
    )
    (net (code "88") (name "unconnected-(U4-AIN7-Pad45)") (class "Default")
      (node (ref "U4") (pin "45") (pinfunction "AIN7_45") (pintype "input"))
    )
    (net (code "89") (name "unconnected-(U4-AIN8-Pad40)") (class "Default")
      (node (ref "U4") (pin "40") (pinfunction "AIN8_40") (pintype "input"))
    )
    (net (code "90") (name "unconnected-(U4-AIN9-Pad39)") (class "Default")
      (node (ref "U4") (pin "39") (pinfunction "AIN9_39") (pintype "input"))
    )
    (net (code "91") (name "unconnected-(U4-AIN10-Pad38)") (class "Default")
      (node (ref "U4") (pin "38") (pinfunction "AIN10_38") (pintype "input"))
    )
    (net (code "92") (name "unconnected-(U4-GPIO3-Pad17)") (class "Default")
      (node (ref "U4") (pin "17") (pinfunction "GPIO3_17") (pintype "bidirectional"))
    )
    (net (code "93") (name "unconnected-(U4-GPIO4-Pad18)") (class "Default")
      (node (ref "U4") (pin "18") (pinfunction "GPIO4_18") (pintype "bidirectional"))
    )
    (net (code "94") (name "unconnected-(U4-GPIO5-Pad19)") (class "Default")
      (node (ref "U4") (pin "19") (pinfunction "GPIO5_19") (pintype "bidirectional"))
    )
    (net (code "95") (name "unconnected-(U4-MUXOUTN-Pad43)") (class "Default")
      (node (ref "U4") (pin "43") (pinfunction "MUXOUTN_43") (pintype "output+no_connect"))
    )
    (net (code "96") (name "unconnected-(U4-MUXOUTP-Pad44)") (class "Default")
      (node (ref "U4") (pin "44") (pinfunction "MUXOUTP_44") (pintype "output+no_connect"))
    )
    (net (code "97") (name "unconnected-(U10-INC-Pad5)") (class "Default")
      (node (ref "U10") (pin "5") (pinfunction "INC_5") (pintype "input"))
    )
    (net (code "98") (name "unconnected-(U10-IND-Pad11)") (class "Default")
      (node (ref "U10") (pin "11") (pinfunction "IND_11") (pintype "input"))
    )
    (net (code "99") (name "unconnected-(U10-OUTC-Pad12)") (class "Default")
      (node (ref "U10") (pin "12") (pinfunction "OUTC_12") (pintype "output"))
    )
    (net (code "100") (name "unconnected-(U10-OUTD-Pad6)") (class "Default")
      (node (ref "U10") (pin "6") (pinfunction "OUTD_6") (pintype "output"))
    )
  )
)
